# cable_tester.net
KiCad netlist of a schematic drawn in EAGLE
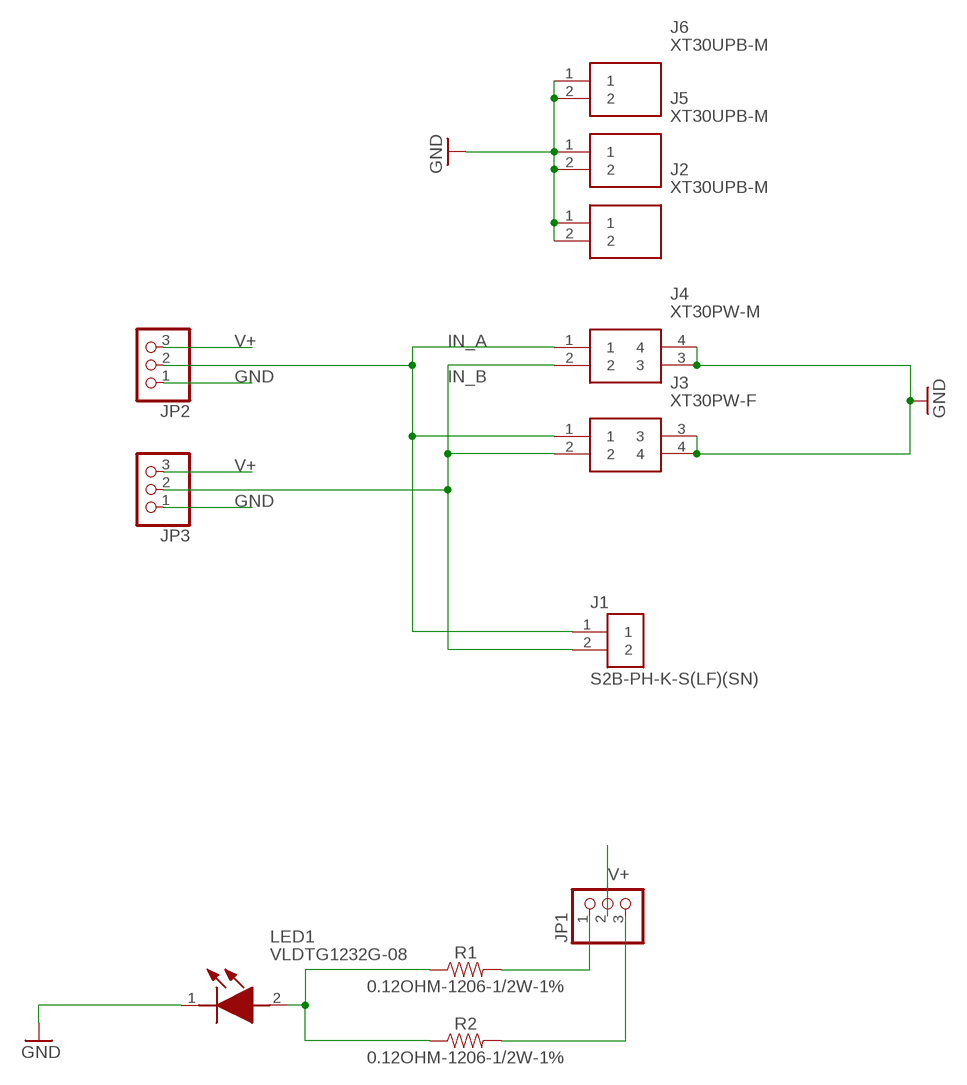
[diagram p0: schematic, sheet 1]

(export (version "E")
  (design (tool "Eeschema 10.0.6"))
  (components
    (comp (ref "J1")
      (value "S2B-PH-K-S(LF)(SN)")
      (footprint "eagle-import:S2B-PH-K-S(LF)(SN)")
      (fields
        (field (name "DIGI_KEY_PART_NUMBER") "455-1719-ND")
        (field (name "MANUFACTURER") "JST Sales America Inc.")
        (field (name "CREATED_BY") "PCBLayout.com")
      )
      (libsource (lib "eagle-import") (part "S2B-PH-K-S(LF)(SN)"))
    )
    (comp (ref "J2")
      (value "XT30UPB-M")
      (footprint "eagle-import:SHDR2W160P0X500_1X2_1020X520X1")
      (libsource (lib "eagle-import") (part "XT30UPB-M"))
    )
    (comp (ref "J3")
      (value "XT30PW-F")
      (footprint "eagle-import:XT30PWF")
      (libsource (lib "eagle-import") (part "XT30PW-F"))
    )
    (comp (ref "J4")
      (value "XT30PW-M")
      (footprint "eagle-import:XT30PWM")
      (libsource (lib "eagle-import") (part "XT30PW-M"))
    )
    (comp (ref "J5")
      (value "XT30UPB-M")
      (footprint "eagle-import:SHDR2W160P0X500_1X2_1020X520X1")
      (libsource (lib "eagle-import") (part "XT30UPB-M"))
    )
    (comp (ref "J6")
      (value "XT30UPB-M")
      (footprint "eagle-import:SHDR2W160P0X500_1X2_1020X520X1")
      (libsource (lib "eagle-import") (part "XT30UPB-M"))
    )
    (comp (ref "JP1")
      (value "PINHD-1X3")
      (footprint "eagle-import:1X03")
      (libsource (lib "eagle-import") (part "PINHD-1X3"))
    )
    (comp (ref "JP2")
      (value "PINHD-1X3")
      (footprint "eagle-import:1X03")
      (libsource (lib "eagle-import") (part "PINHD-1X3"))
    )
    (comp (ref "JP3")
      (value "PINHD-1X3")
      (footprint "eagle-import:1X03")
      (libsource (lib "eagle-import") (part "PINHD-1X3"))
    )
    (comp (ref "LED1")
      (value "VLDTG1232G-08")
      (footprint "eagle-import:VLDTG1232G08")
      (fields (field (name "MOUSER_PART_NUMBER") "78-VLDTG1232G-08"))
      (libsource (lib "eagle-import") (part "VLDTG1232G-08"))
    )
    (comp (ref "R1")
      (value "0.12OHM-1206-1/2W-1%")
      (footprint "eagle-import:1206")
      (libsource (lib "eagle-import") (part "0.12OHM-1206-1/2W-1%"))
    )
    (comp (ref "R2")
      (value "0.12OHM-1206-1/2W-1%")
      (footprint "eagle-import:1206")
      (libsource (lib "eagle-import") (part "0.12OHM-1206-1/2W-1%"))
    )
  )
  (nets
    (net (code "1") (name "/IN_A") (class "Default")
      (node (ref "J1") (pin "1") (pinfunction "1_1") (pintype "passive"))
      (node (ref "J3") (pin "1") (pinfunction "1_1") (pintype "bidirectional"))
      (node (ref "J4") (pin "1") (pinfunction "1_1") (pintype "bidirectional"))
      (node (ref "JP2") (pin "2") (pinfunction "2_2") (pintype "passive"))
    )
    (net (code "2") (name "/IN_B") (class "Default")
      (node (ref "J1") (pin "2") (pinfunction "2_2") (pintype "passive"))
      (node (ref "J3") (pin "2") (pinfunction "2_2") (pintype "bidirectional"))
      (node (ref "J4") (pin "2") (pinfunction "2_2") (pintype "bidirectional"))
      (node (ref "JP3") (pin "2") (pinfunction "2_2") (pintype "passive"))
    )
    (net (code "3") (name "/V+") (class "Default")
      (node (ref "JP1") (pin "2") (pinfunction "2_2") (pintype "passive"))
      (node (ref "JP2") (pin "3") (pinfunction "3_3") (pintype "passive"))
      (node (ref "JP3") (pin "3") (pinfunction "3_3") (pintype "passive"))
    )
    (net (code "4") (name "GND") (class "Default")
      (node (ref "J2") (pin "1") (pinfunction "1_1") (pintype "bidirectional"))
      (node (ref "J2") (pin "2") (pinfunction "2_2") (pintype "bidirectional"))
      (node (ref "J3") (pin "3") (pinfunction "3_3") (pintype "bidirectional"))
      (node (ref "J3") (pin "4") (pinfunction "4_4") (pintype "bidirectional"))
      (node (ref "J4") (pin "3") (pinfunction "3_3") (pintype "bidirectional"))
      (node (ref "J4") (pin "4") (pinfunction "4_4") (pintype "bidirectional"))
      (node (ref "J5") (pin "1") (pinfunction "1_1") (pintype "bidirectional"))
      (node (ref "J5") (pin "2") (pinfunction "2_2") (pintype "bidirectional"))
      (node (ref "J6") (pin "1") (pinfunction "1_1") (pintype "bidirectional"))
      (node (ref "J6") (pin "2") (pinfunction "2_2") (pintype "bidirectional"))
      (node (ref "JP2") (pin "1") (pinfunction "1_1") (pintype "passive"))
      (node (ref "JP3") (pin "1") (pinfunction "1_1") (pintype "passive"))
      (node (ref "LED1") (pin "1") (pinfunction "K_1") (pintype "bidirectional"))
    )
    (net (code "5") (name "Net-(JP1-Pad1)") (class "Default")
      (node (ref "JP1") (pin "1") (pinfunction "1_1") (pintype "passive"))
      (node (ref "R1") (pin "2") (pinfunction "2_2") (pintype "passive"))
    )
    (net (code "6") (name "Net-(JP1-Pad3)") (class "Default")
      (node (ref "JP1") (pin "3") (pinfunction "3_3") (pintype "passive"))
      (node (ref "R2") (pin "2") (pinfunction "2_2") (pintype "passive"))
    )
    (net (code "7") (name "Net-(LED1-A)") (class "Default")
      (node (ref "LED1") (pin "2") (pinfunction "A_2") (pintype "bidirectional"))
      (node (ref "R1") (pin "1") (pinfunction "1_1") (pintype "passive"))
      (node (ref "R2") (pin "1") (pinfunction "1_1") (pintype "passive"))
    )
  )
)
